# ZLG_CandleLight_F072.net
KiCad netlist of a schematic drawn in Altium Designer
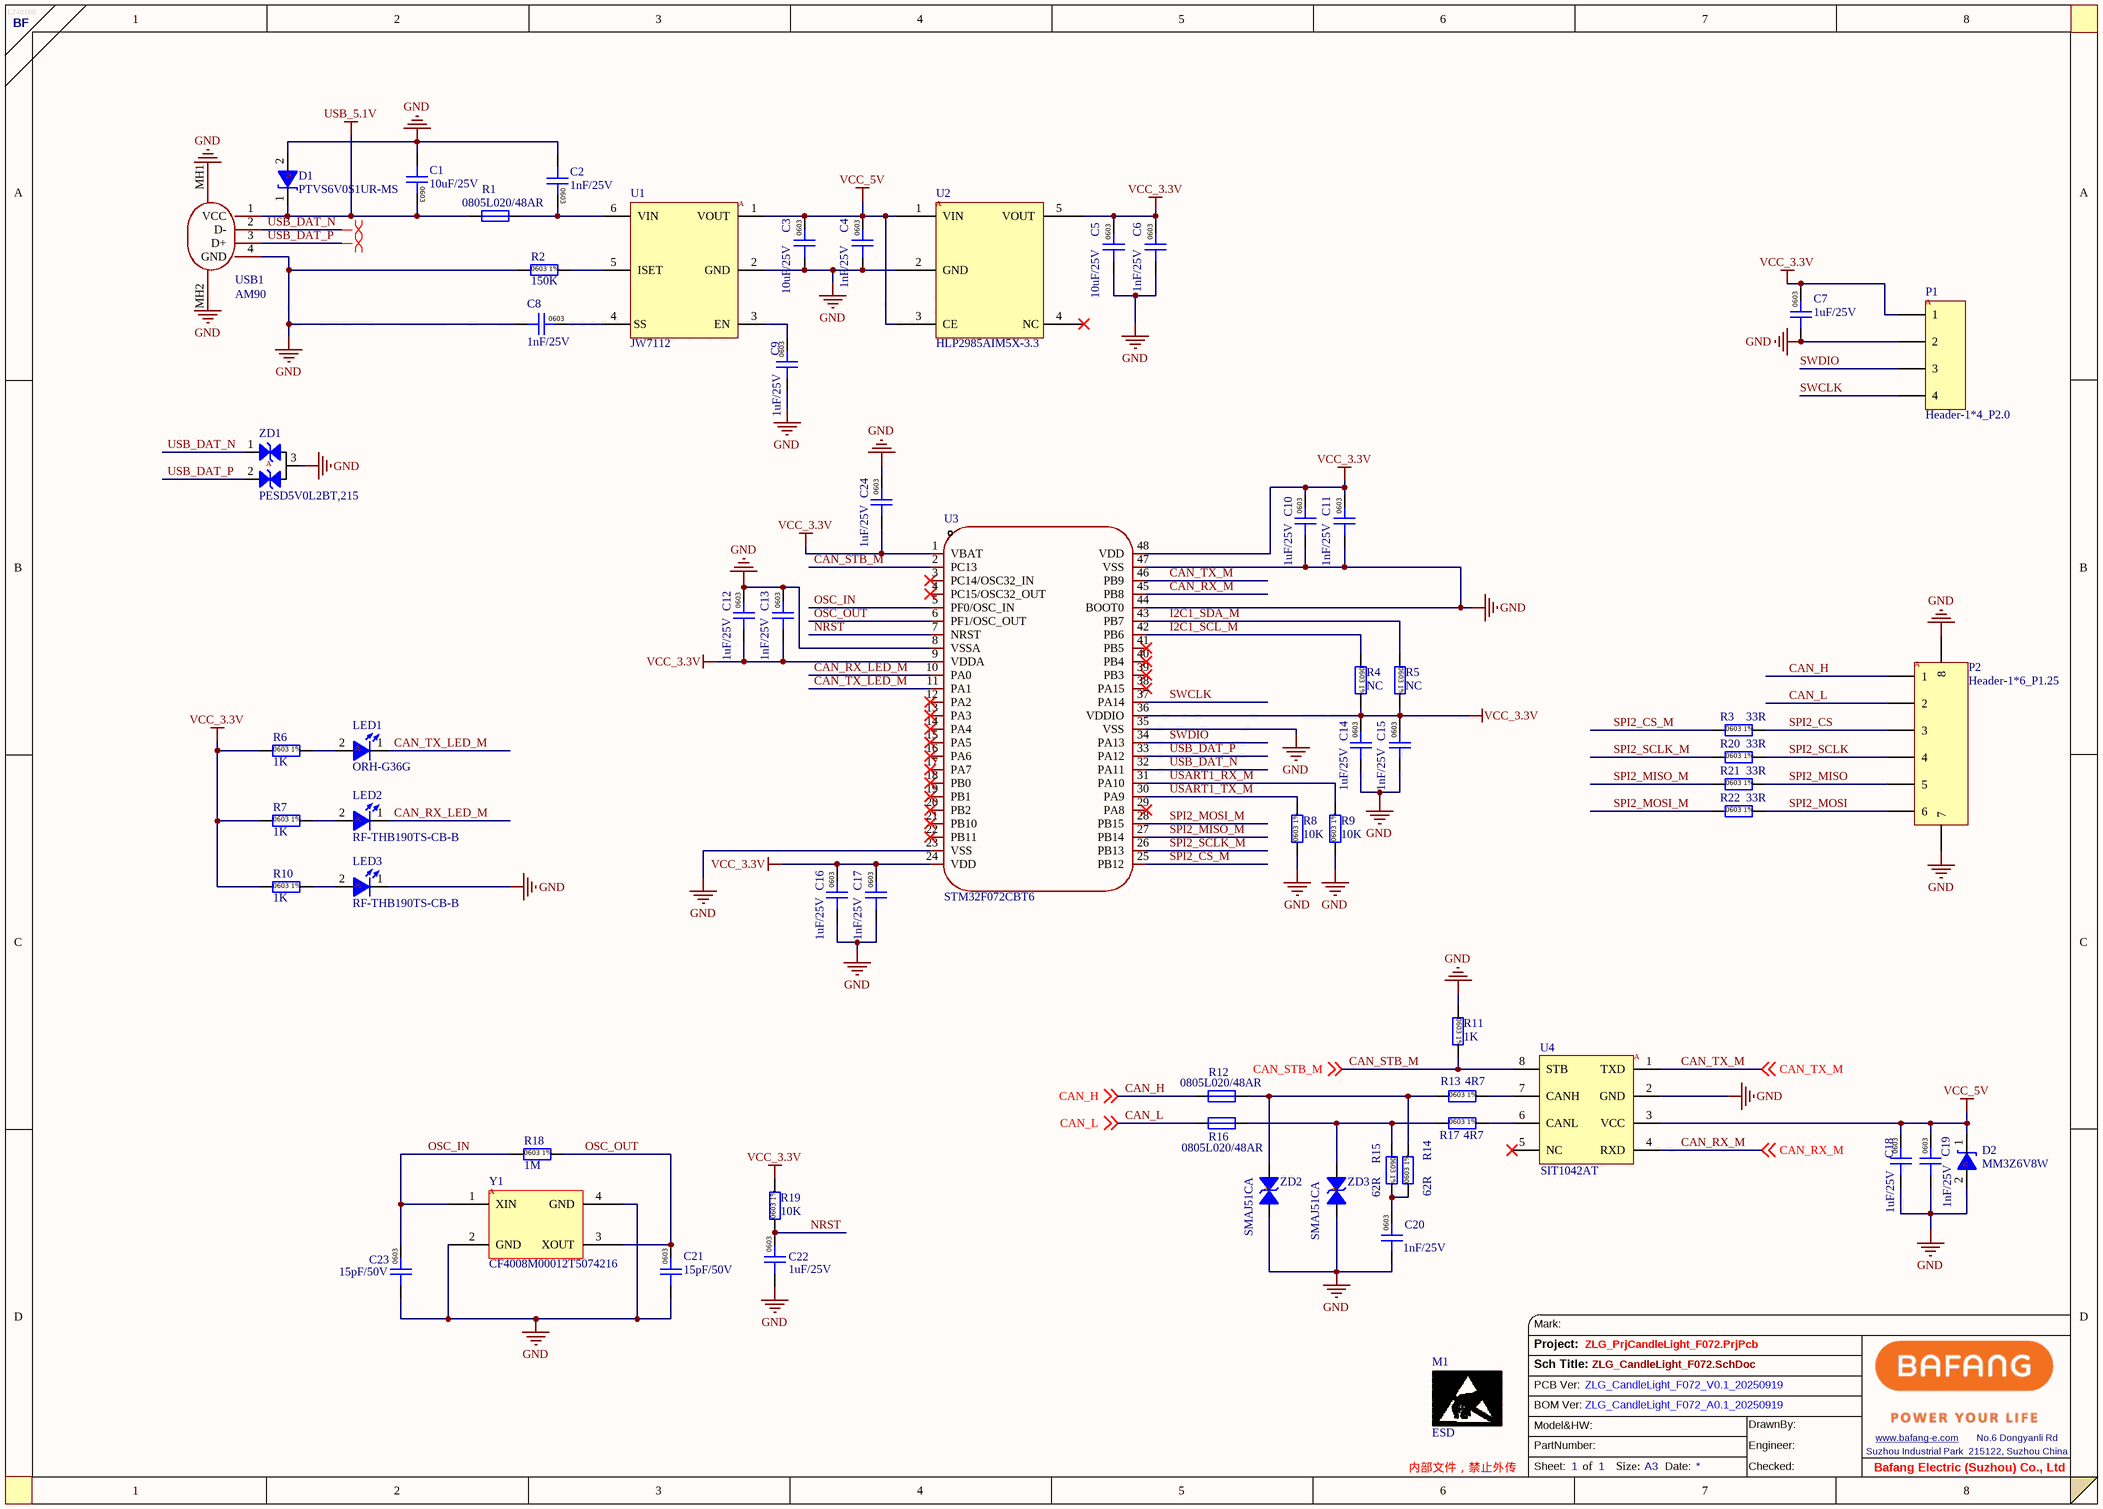
[diagram p0: ZLG_CandleLight_F072.SchDoc]

(export (version "E")
  (design (tool "Eeschema 10.0.6"))
  (components
    (comp (ref "C1")
      (value "10uF/25V")
      (footprint "C-0603")
      (description "10μF, 25V, ±10%, -55to85℃")
      (libsource (lib "Database_Lib") (part "CC0603K106-8"))
    )
    (comp (ref "C2")
      (value "1nF/25V")
      (footprint "C-0603")
      (description "1nF, 25V, ±10%, -55to125℃")
      (libsource (lib "Database_Lib") (part "CC0603K102-8"))
    )
    (comp (ref "C3")
      (value "10uF/25V")
      (footprint "C-0603")
      (description "10μF, 25V, ±10%, -55to85℃")
      (libsource (lib "Database_Lib") (part "CC0603K106-8"))
    )
    (comp (ref "C4")
      (value "1nF/25V")
      (footprint "C-0603")
      (description "1nF, 25V, ±10%, -55to125℃")
      (libsource (lib "Database_Lib") (part "CC0603K102-8"))
    )
    (comp (ref "C5")
      (value "10uF/25V")
      (footprint "C-0603")
      (description "10μF, 25V, ±10%, -55to85℃")
      (libsource (lib "Database_Lib") (part "CC0603K106-8"))
    )
    (comp (ref "C6")
      (value "1nF/25V")
      (footprint "C-0603")
      (description "1nF, 25V, ±10%, -55to125℃")
      (libsource (lib "Database_Lib") (part "CC0603K102-8"))
    )
    (comp (ref "C7")
      (value "1uF/25V")
      (footprint "C-0603")
      (description "1μF, 25V, ±10%, -55to125℃")
      (libsource (lib "Database_Lib") (part "CC0603K105-8"))
    )
    (comp (ref "C8")
      (value "1nF/25V")
      (footprint "C-0603")
      (description "1nF, 25V, ±10%, -55to125℃")
      (libsource (lib "Database_Lib") (part "CC0603K102-8"))
    )
    (comp (ref "C9")
      (value "1uF/25V")
      (footprint "C-0603")
      (description "1μF, 25V, ±10%, -55to125℃")
      (libsource (lib "Database_Lib") (part "CC0603K105-8"))
    )
    (comp (ref "C10")
      (value "1uF/25V")
      (footprint "C-0603")
      (description "1μF, 25V, ±10%, -55to125℃")
      (libsource (lib "Database_Lib") (part "CC0603K105-8"))
    )
    (comp (ref "C11")
      (value "1nF/25V")
      (footprint "C-0603")
      (description "1nF, 25V, ±10%, -55to125℃")
      (libsource (lib "Database_Lib") (part "CC0603K102-8"))
    )
    (comp (ref "C12")
      (value "1uF/25V")
      (footprint "C-0603")
      (description "1μF, 25V, ±10%, -55to125℃")
      (libsource (lib "Database_Lib") (part "CC0603K105-8"))
    )
    (comp (ref "C13")
      (value "1nF/25V")
      (footprint "C-0603")
      (description "1nF, 25V, ±10%, -55to125℃")
      (libsource (lib "Database_Lib") (part "CC0603K102-8"))
    )
    (comp (ref "C14")
      (value "1uF/25V")
      (footprint "C-0603")
      (description "1μF, 25V, ±10%, -55to125℃")
      (libsource (lib "Database_Lib") (part "CC0603K105-8"))
    )
    (comp (ref "C15")
      (value "1nF/25V")
      (footprint "C-0603")
      (description "1nF, 25V, ±10%, -55to125℃")
      (libsource (lib "Database_Lib") (part "CC0603K102-8"))
    )
    (comp (ref "C16")
      (value "1uF/25V")
      (footprint "C-0603")
      (description "1μF, 25V, ±10%, -55to125℃")
      (libsource (lib "Database_Lib") (part "CC0603K105-8"))
    )
    (comp (ref "C17")
      (value "1nF/25V")
      (footprint "C-0603")
      (description "1nF, 25V, ±10%, -55to125℃")
      (libsource (lib "Database_Lib") (part "CC0603K102-8"))
    )
    (comp (ref "C18")
      (value "1uF/25V")
      (footprint "C-0603")
      (description "1μF, 25V, ±10%, -55to125℃")
      (libsource (lib "Database_Lib") (part "CC0603K105-8"))
    )
    (comp (ref "C19")
      (value "1nF/25V")
      (footprint "C-0603")
      (description "1nF, 25V, ±10%, -55to125℃")
      (libsource (lib "Database_Lib") (part "CC0603K102-8"))
    )
    (comp (ref "C20")
      (value "1nF/25V")
      (footprint "C-0603")
      (description "1nF, 25V, ±10%, -55to125℃")
      (libsource (lib "Database_Lib") (part "CC0603K102-8"))
    )
    (comp (ref "C21")
      (value "15pF/50V")
      (footprint "C-0603")
      (description "15pF, 50V, ±5%,, -55to125℃")
      (libsource (lib "Database_Lib") (part "CC0603J150-9"))
    )
    (comp (ref "C22")
      (value "1uF/25V")
      (footprint "C-0603")
      (description "1μF, 25V, ±10%, -55to125℃")
      (libsource (lib "Database_Lib") (part "CC0603K105-8"))
    )
    (comp (ref "C23")
      (value "15pF/50V")
      (footprint "C-0603")
      (description "15pF, 50V, ±5%,, -55to125℃")
      (libsource (lib "Database_Lib") (part "CC0603J150-9"))
    )
    (comp (ref "C24")
      (value "1uF/25V")
      (footprint "C-0603")
      (description "1μF, 25V, ±10%, -55to125℃")
      (libsource (lib "Database_Lib") (part "CC0603K105-8"))
    )
    (comp (ref "D1")
      (value "PTVS6V0S1UR-MS")
      (footprint "SOD-123W")
      (description "TVS管 VR=6V,峰值脉冲电流（IPP）=38.84A,最大钳位电压:：10.3V")
      (fields
        (field (name "COMPONENTLINK1URL") "O:\\ECU\\B02_Hardware硬件\\A02_Libraries 原理图PCB封装库\\Datasheet\\Semicon\\TVS二极管_PTVS5V0S1UR-MS.PDF")
      )
      (libsource (lib "Database_Lib") (part "PTVS6V0S1UR-MS"))
    )
    (comp (ref "D2")
      (value "MM3Z6V8W")
      (footprint "SOD-123")
      (description "稳压二极管   Vzt:6.8V,  ±5%    0.5W  Izt:5mA,-65to150℃")
      (fields
        (field (name "MPN") "MM1Z6V8W")
        (field (name "COMPONENTLINK1URL") "O:\\ECU\\B02_Hardware硬件\\A02_Libraries 原理图PCB封装库\\Datasheet\\Semicon\\稳压二极管_MM1Z2V0W-MM1Z75W.pdf")
      )
      (libsource (lib "Database_Lib") (part "MM1Z6V8W"))
    )
    (comp (ref "LED1")
      (value "ORH-G36G")
      (footprint "LED-SMT-0603")
      (description "发光二极管  GREEN, 2.8V, 30mA, -25to80℃")
      (fields
        (field (name "COMPONENTLINK1URL") "O:\\ECU\\B02_Hardware硬件\\A02_Libraries 原理图PCB封装库\\Datasheet\\Semicon\\发光二极管_ORH-G36G.pdf")
      )
      (libsource (lib "Database_Lib") (part "ORH-G36G"))
    )
    (comp (ref "LED2")
      (value "RF-THB190TS-CB-B")
      (footprint "LED-SMT-0603")
      (description "发光二极管  GREEN, 2.8V, -40to85℃")
      (fields
        (field (name "COMPONENTLINK1URL") "O:\\ECU\\B02_Hardware硬件\\A02_Libraries 原理图PCB封装库\\Datasheet\\Semicon\\发光二极管_RF-THB190TS-CB-B.pdf")
      )
      (libsource (lib "Database_Lib") (part "RF-THB190TS-CB-B"))
    )
    (comp (ref "LED3")
      (value "RF-THB190TS-CB-B")
      (footprint "LED-SMT-0603")
      (description "发光二极管  GREEN, 2.8V, -40to85℃")
      (fields
        (field (name "COMPONENTLINK1URL") "O:\\ECU\\B02_Hardware硬件\\A02_Libraries 原理图PCB封装库\\Datasheet\\Semicon\\发光二极管_RF-THB190TS-CB-B.pdf")
      )
      (libsource (lib "Database_Lib") (part "RF-THB190TS-CB-B"))
    )
    (comp (ref "M1") (value "ESD") (footprint "ESD-5*4mm") (libsource (lib "Database_Lib") (part "ESD")))
    (comp (ref "P1")
      (value "Header-1*4_P2.0")
      (footprint "CON-1*4-P2.0-Download")
      (description "Header, 4Pin .P2.0")
      (libsource (lib "Database_Lib") (part "Header-1*4_P2.0"))
    )
    (comp (ref "P2")
      (value "Header-1*6_P1.25")
      (footprint "CON-1*6-P1.25")
      (description "Header, 6Pin, P1.25")
      (fields
        (field (name "MPN") "A12514WR-S-06PNLNT1T00R")
        (field (name "COMPONENTLINK1URL") "O:\\ECU\\B02_Hardware硬件\\A02_Libraries 原理图PCB封装库\\Datasheet\\Connectors\\线对板针座_A12514WR-S-06PNLNT1T00R.PDF")
      )
      (libsource (lib "Database_Lib") (part "Header-1*6_P1.25"))
    )
    (comp (ref "R1")
      (value "0805L020/48AR")
      (footprint "R-0805")
      (description "自恢复保险丝  耐压: 48V  最大电流: 40A  保持电流(Ih): 200mA  跳闸电流: 500mA")
      (fields
        (field (name "COMPONENTLINK1URL") "O:\\ECU\\B02_Hardware硬件\\A02_Libraries 原理图PCB封装库\\Datasheet\\RLC\\自恢复保险丝_0805L020-48AR.PDF")
      )
      (libsource (lib "Database_Lib") (part "F0805-020-48V"))
    )
    (comp (ref "R2")
      (value "150K")
      (footprint "R-0603")
      (description "150KΩ, 0.1W, 1%, -55to155℃")
      (libsource (lib "Database_Lib") (part "RC0603F150K"))
    )
    (comp (ref "R3")
      (value "33R")
      (footprint "R-0603")
      (description "33Ω, 0.1W, 1%, -55to155℃")
      (libsource (lib "Database_Lib") (part "RC0603F33R"))
    )
    (comp (ref "R4")
      (value "NC")
      (footprint "R-0603")
      (description "10KΩ, 0.1W, 1%, -55to155℃")
      (libsource (lib "Database_Lib") (part "RC0603F10K"))
    )
    (comp (ref "R5")
      (value "NC")
      (footprint "R-0603")
      (description "10KΩ, 0.1W, 1%, -55to155℃")
      (libsource (lib "Database_Lib") (part "RC0603F10K"))
    )
    (comp (ref "R6")
      (value "1K")
      (footprint "R-0603")
      (description "1KΩ, 0.1W, 1%, -55to155℃")
      (libsource (lib "") (part "RC0603F1K_1"))
    )
    (comp (ref "R7")
      (value "1K")
      (footprint "R-0603")
      (description "1KΩ, 0.1W, 1%, -55to155℃")
      (libsource (lib "") (part "RC0603F1K_1"))
    )
    (comp (ref "R8")
      (value "10K")
      (footprint "R-0603")
      (description "10KΩ, 0.1W, 1%, -55to155℃")
      (libsource (lib "") (part "RC0603F10K_1"))
    )
    (comp (ref "R9")
      (value "10K")
      (footprint "R-0603")
      (description "10KΩ, 0.1W, 1%, -55to155℃")
      (libsource (lib "") (part "RC0603F10K_1"))
    )
    (comp (ref "R10")
      (value "1K")
      (footprint "R-0603")
      (description "1KΩ, 0.1W, 1%, -55to155℃")
      (libsource (lib "") (part "RC0603F1K_1"))
    )
    (comp (ref "R11")
      (value "1K")
      (footprint "R-0603")
      (description "1KΩ, 0.1W, 1%, -55to155℃")
      (libsource (lib "Database_Lib") (part "RC0603F1K"))
    )
    (comp (ref "R12")
      (value "0805L020/48AR")
      (footprint "R-0805")
      (description "自恢复保险丝  耐压: 48V  最大电流: 40A  保持电流(Ih): 200mA  跳闸电流: 500mA")
      (fields
        (field (name "COMPONENTLINK1URL") "O:\\ECU\\B02_Hardware硬件\\A02_Libraries 原理图PCB封装库\\Datasheet\\RLC\\自恢复保险丝_0805L020-48AR.PDF")
      )
      (libsource (lib "Database_Lib") (part "F0805-020-48V"))
    )
    (comp (ref "R13")
      (value "4R7")
      (footprint "R-0603")
      (description "4.7Ω, 0.1W, 1%, -55to155℃")
      (libsource (lib "Database_Lib") (part "RC0603F4R7"))
    )
    (comp (ref "R14")
      (value "62R")
      (footprint "R-0603")
      (description "62Ω, 0.1W, 1%, -55to155℃")
      (libsource (lib "Database_Lib") (part "RC0603F62R"))
    )
    (comp (ref "R15")
      (value "62R")
      (footprint "R-0603")
      (description "62Ω, 0.1W, 1%, -55to155℃")
      (libsource (lib "") (part "RC0603F62R_1"))
    )
    (comp (ref "R16")
      (value "0805L020/48AR")
      (footprint "R-0805")
      (description "自恢复保险丝  耐压: 48V  最大电流: 40A  保持电流(Ih): 200mA  跳闸电流: 500mA")
      (fields
        (field (name "COMPONENTLINK1URL") "O:\\ECU\\B02_Hardware硬件\\A02_Libraries 原理图PCB封装库\\Datasheet\\RLC\\自恢复保险丝_0805L020-48AR.PDF")
      )
      (libsource (lib "Database_Lib") (part "F0805-020-48V"))
    )
    (comp (ref "R17")
      (value "4R7")
      (footprint "R-0603")
      (description "4.7Ω, 0.1W, 1%, -55to155℃")
      (libsource (lib "Database_Lib") (part "RC0603F4R7"))
    )
    (comp (ref "R18")
      (value "1M")
      (footprint "R-0603")
      (description "1MΩ, 0.1W, 1%, -55to155℃")
      (libsource (lib "Database_Lib") (part "RC0603F1M"))
    )
    (comp (ref "R19")
      (value "10K")
      (footprint "R-0603")
      (description "10KΩ, 0.1W, 1%, -55to155℃")
      (libsource (lib "") (part "RC0603F10K_1"))
    )
    (comp (ref "R20")
      (value "33R")
      (footprint "R-0603")
      (description "33Ω, 0.1W, 1%, -55to155℃")
      (libsource (lib "Database_Lib") (part "RC0603F33R"))
    )
    (comp (ref "R21")
      (value "33R")
      (footprint "R-0603")
      (description "33Ω, 0.1W, 1%, -55to155℃")
      (libsource (lib "Database_Lib") (part "RC0603F33R"))
    )
    (comp (ref "R22")
      (value "33R")
      (footprint "R-0603")
      (description "33Ω, 0.1W, 1%, -55to155℃")
      (libsource (lib "Database_Lib") (part "RC0603F33R"))
    )
    (comp (ref "U1")
      (value "JW7112")
      (footprint "SOT-23-6")
      (description "高边热插拔控制器   工作电压范围：2.8V至16V，导通电阻：50mΩ，最大3A可持续电流")
      (fields
        (field (name "COMPONENTLINK1URL") "O:\\ECU\\B02_Hardware硬件\\A02_Libraries 原理图PCB封装库\\Datasheet\\IC\\高边热插拔控制器_JW7112.pdf")
      )
      (libsource (lib "Database_Lib") (part "JW7112"))
    )
    (comp (ref "U2")
      (value "HLP2985AIM5X-3.3")
      (footprint "SOT-23-5")
      (description "LDO,工作电压16V，输出电压3.3V，输出电流150mA，-40℃~+125℃")
      (fields
        (field (name "COMPONENTLINK1URL") "O:\\ECU\\B02_Hardware硬件\\A02_Libraries 原理图PCB封装库\\Datasheet\\IC\\LDO_HLP2985AIM5X-3.3.pdf")
      )
      (libsource (lib "Database_Lib") (part "HLP2985AIM5X-3.3"))
    )
    (comp (ref "U3")
      (value "STM32F072CBT6")
      (footprint "LQFP-48_L7.0-W7.0-P0.50-LS9.0-BL")
      (fields (field (name "MANUFACTURER") "ST(意法半导体)"))
      (libsource (lib "ZLG_CandleLight_F072") (part "STM32F072CBT6"))
    )
    (comp (ref "U4")
      (value "SIT1042AT")
      (footprint "SOP-8")
      (description "CAN芯片   5V 供电，±70V 总线耐压，待机模式CAN FD 总线收发器")
      (fields
        (field (name "COMPONENTLINK1URL") "O:\\ECU\\B02_Hardware硬件\\A02_Libraries 原理图PCB封装库\\Datasheet\\IC\\CAN芯片_SIT1042AT.pdf")
      )
      (libsource (lib "Database_Lib") (part "SIT1042AT"))
    )
    (comp (ref "USB1")
      (value "AM90")
      (footprint "USB-AM-TH_AM90")
      (fields (field (name "MANUFACTURER") "SHOU HAN(首韩)"))
      (libsource (lib "ZLG_CandleLight_F072") (part "AM90"))
    )
    (comp (ref "Y1")
      (value "CF4008M00012T5074216")
      (footprint "CRYSTAL-SMT_3225-4P")
      (description "8MHZ,SMD_3225,贴片无源晶振")
      (fields
        (field (name "COMPONENTLINK1URL") "O:\\ECU\\B02_Hardware硬件\\A02_Libraries 原理图PCB封装库\\Datasheet\\Semicon\\晶振_CF4008M00012T5074216.PDF")
      )
      (libsource (lib "Database_Lib") (part "CF4008M00012T5074216"))
    )
    (comp (ref "ZD1")
      (value "PESD5V0L2BT,215")
      (footprint "SOT-23-3")
      (description "静电放电(ESD)保护管  Vbr:8.2V, Vrwm:5V, TVS二极管 1uA 5V, -65°C-150°C,")
      (fields
        (field (name "COMPONENTLINK1URL") "O:\\ECU\\B02_Hardware硬件\\A02_Libraries 原理图PCB封装库\\Datasheet\\Semicon\\TVS二极管_PESD5V0L2BT,215.pdf")
      )
      (libsource (lib "Database_Lib") (part "PESD5V0L2BT,215"))
    )
    (comp (ref "ZD2")
      (value "SMAJ51CA")
      (footprint "SMA(DO-214AC)")
      (fields
        (field (name "COMPONENTLINK1URL") "O:\\ECU\\B02_Hardware硬件\\A02_Libraries 原理图PCB封装库\\Datasheet\\Semicon\\TVS二极管_SMAJ51CA.pdf")
      )
      (libsource (lib "Database_Lib") (part "SMAJ51CA"))
    )
    (comp (ref "ZD3")
      (value "SMAJ51CA")
      (footprint "SMA(DO-214AC)")
      (fields
        (field (name "COMPONENTLINK1URL") "O:\\ECU\\B02_Hardware硬件\\A02_Libraries 原理图PCB封装库\\Datasheet\\Semicon\\TVS二极管_SMAJ51CA.pdf")
      )
      (libsource (lib "Database_Lib") (part "SMAJ51CA"))
    )
  )
  (nets
    (net (code "1") (name "/CAN_RX_LED_M") (class "Default")
      (node (ref "LED2") (pin "1") (pinfunction "C_1") (pintype "passive"))
      (node (ref "U3") (pin "10") (pinfunction "PA0_10") (pintype "passive"))
    )
    (net (code "2") (name "/CAN_TX_LED_M") (class "Default")
      (node (ref "LED1") (pin "1") (pinfunction "C_1") (pintype "passive"))
      (node (ref "U3") (pin "11") (pinfunction "PA1_11") (pintype "passive"))
    )
    (net (code "3") (name "/I2C1_SCL_M") (class "Default")
      (node (ref "R4") (pin "1") (pinfunction "1_1") (pintype "passive"))
      (node (ref "U3") (pin "42") (pinfunction "PB6_42") (pintype "passive"))
    )
    (net (code "4") (name "/I2C1_SDA_M") (class "Default")
      (node (ref "R5") (pin "1") (pinfunction "1_1") (pintype "passive"))
      (node (ref "U3") (pin "43") (pinfunction "PB7_43") (pintype "passive"))
    )
    (net (code "5") (name "/NRST") (class "Default")
      (node (ref "C22") (pin "2") (pinfunction "2_2") (pintype "passive"))
      (node (ref "R19") (pin "1") (pinfunction "1_1") (pintype "passive"))
      (node (ref "U3") (pin "7") (pinfunction "NRST_7") (pintype "passive"))
    )
    (net (code "6") (name "/OSC_IN") (class "Default")
      (node (ref "C23") (pin "2") (pinfunction "2_2") (pintype "passive"))
      (node (ref "R18") (pin "1") (pinfunction "1_1") (pintype "passive"))
      (node (ref "U3") (pin "5") (pinfunction "PF0/OSC_IN_5") (pintype "passive"))
      (node (ref "Y1") (pin "1") (pinfunction "XIN_1") (pintype "passive"))
    )
    (net (code "7") (name "/OSC_OUT") (class "Default")
      (node (ref "C21") (pin "2") (pinfunction "2_2") (pintype "passive"))
      (node (ref "R18") (pin "2") (pinfunction "2_2") (pintype "passive"))
      (node (ref "U3") (pin "6") (pinfunction "PF1/OSC_OUT_6") (pintype "passive"))
      (node (ref "Y1") (pin "3") (pinfunction "XOUT_3") (pintype "passive"))
    )
    (net (code "8") (name "/SPI2_CS") (class "Default")
      (node (ref "P2") (pin "3") (pinfunction "3_3") (pintype "passive"))
      (node (ref "R3") (pin "2") (pinfunction "2_2") (pintype "passive"))
    )
    (net (code "9") (name "/SPI2_CS_M") (class "Default")
      (node (ref "R3") (pin "1") (pinfunction "1_1") (pintype "passive"))
      (node (ref "U3") (pin "25") (pinfunction "PB12_25") (pintype "passive"))
    )
    (net (code "10") (name "/SPI2_MISO") (class "Default")
      (node (ref "P2") (pin "5") (pinfunction "5_5") (pintype "passive"))
      (node (ref "R21") (pin "2") (pinfunction "2_2") (pintype "passive"))
    )
    (net (code "11") (name "/SPI2_MISO_M") (class "Default")
      (node (ref "R21") (pin "1") (pinfunction "1_1") (pintype "passive"))
      (node (ref "U3") (pin "27") (pinfunction "PB14_27") (pintype "passive"))
    )
    (net (code "12") (name "/SPI2_MOSI") (class "Default")
      (node (ref "P2") (pin "6") (pinfunction "6_6") (pintype "passive"))
      (node (ref "R22") (pin "2") (pinfunction "2_2") (pintype "passive"))
    )
    (net (code "13") (name "/SPI2_MOSI_M") (class "Default")
      (node (ref "R22") (pin "1") (pinfunction "1_1") (pintype "passive"))
      (node (ref "U3") (pin "28") (pinfunction "PB15_28") (pintype "passive"))
    )
    (net (code "14") (name "/SPI2_SCLK") (class "Default")
      (node (ref "P2") (pin "4") (pinfunction "4_4") (pintype "passive"))
      (node (ref "R20") (pin "2") (pinfunction "2_2") (pintype "passive"))
    )
    (net (code "15") (name "/SPI2_SCLK_M") (class "Default")
      (node (ref "R20") (pin "1") (pinfunction "1_1") (pintype "passive"))
      (node (ref "U3") (pin "26") (pinfunction "PB13_26") (pintype "passive"))
    )
    (net (code "16") (name "/SWCLK") (class "Default")
      (node (ref "P1") (pin "4") (pinfunction "4_4") (pintype "passive"))
      (node (ref "U3") (pin "37") (pinfunction "PA14_37") (pintype "passive"))
    )
    (net (code "17") (name "/SWDIO") (class "Default")
      (node (ref "P1") (pin "3") (pinfunction "3_3") (pintype "passive"))
      (node (ref "U3") (pin "34") (pinfunction "PA13_34") (pintype "passive"))
    )
    (net (code "18") (name "/USART1_RX_M") (class "Default")
      (node (ref "R9") (pin "2") (pinfunction "2_2") (pintype "passive"))
      (node (ref "U3") (pin "31") (pinfunction "PA10_31") (pintype "passive"))
    )
    (net (code "19") (name "/USART1_TX_M") (class "Default")
      (node (ref "R8") (pin "2") (pinfunction "2_2") (pintype "passive"))
      (node (ref "U3") (pin "30") (pinfunction "PA9_30") (pintype "passive"))
    )
    (net (code "20") (name "/USB_DAT_N") (class "Default")
      (node (ref "U3") (pin "32") (pinfunction "PA11_32") (pintype "passive"))
      (node (ref "USB1") (pin "2") (pinfunction "D-_2") (pintype "passive"))
      (node (ref "ZD1") (pin "1") (pinfunction "1_1") (pintype "passive"))
    )
    (net (code "21") (name "/USB_DAT_P") (class "Default")
      (node (ref "U3") (pin "33") (pinfunction "PA12_33") (pintype "passive"))
      (node (ref "USB1") (pin "3") (pinfunction "D+_3") (pintype "passive"))
      (node (ref "ZD1") (pin "2") (pinfunction "2_2") (pintype "passive"))
    )
    (net (code "22") (name "CAN_H") (class "Default")
      (node (ref "P2") (pin "1") (pinfunction "1_1") (pintype "passive"))
      (node (ref "R12") (pin "1") (pinfunction "1_1") (pintype "passive"))
    )
    (net (code "23") (name "CAN_L") (class "Default")
      (node (ref "P2") (pin "2") (pinfunction "2_2") (pintype "passive"))
      (node (ref "R16") (pin "1") (pinfunction "1_1") (pintype "passive"))
    )
    (net (code "24") (name "CAN_RX_M") (class "Default")
      (node (ref "U3") (pin "45") (pinfunction "PB8_45") (pintype "passive"))
      (node (ref "U4") (pin "4") (pinfunction "RXD_4") (pintype "passive"))
    )
    (net (code "25") (name "CAN_STB_M") (class "Default")
      (node (ref "R11") (pin "2") (pinfunction "2_2") (pintype "passive"))
      (node (ref "U3") (pin "2") (pinfunction "PC13_2") (pintype "passive"))
      (node (ref "U4") (pin "8") (pinfunction "STB_8") (pintype "passive"))
    )
    (net (code "26") (name "CAN_TX_M") (class "Default")
      (node (ref "U3") (pin "46") (pinfunction "PB9_46") (pintype "passive"))
      (node (ref "U4") (pin "1") (pinfunction "TXD_1") (pintype "passive"))
    )
    (net (code "27") (name "GND") (class "Default")
      (node (ref "C1") (pin "1") (pinfunction "1_1") (pintype "passive"))
      (node (ref "C10") (pin "1") (pinfunction "1_1") (pintype "passive"))
      (node (ref "C11") (pin "1") (pinfunction "1_1") (pintype "passive"))
      (node (ref "C12") (pin "2") (pinfunction "2_2") (pintype "passive"))
      (node (ref "C13") (pin "2") (pinfunction "2_2") (pintype "passive"))
      (node (ref "C14") (pin "1") (pinfunction "1_1") (pintype "passive"))
      (node (ref "C15") (pin "1") (pinfunction "1_1") (pintype "passive"))
      (node (ref "C16") (pin "1") (pinfunction "1_1") (pintype "passive"))
      (node (ref "C17") (pin "1") (pinfunction "1_1") (pintype "passive"))
      (node (ref "C18") (pin "1") (pinfunction "1_1") (pintype "passive"))
      (node (ref "C19") (pin "1") (pinfunction "1_1") (pintype "passive"))
      (node (ref "C2") (pin "1") (pinfunction "1_1") (pintype "passive"))
      (node (ref "C20") (pin "1") (pinfunction "1_1") (pintype "passive"))
      (node (ref "C21") (pin "1") (pinfunction "1_1") (pintype "passive"))
      (node (ref "C22") (pin "1") (pinfunction "1_1") (pintype "passive"))
      (node (ref "C23") (pin "1") (pinfunction "1_1") (pintype "passive"))
      (node (ref "C24") (pin "2") (pinfunction "2_2") (pintype "passive"))
      (node (ref "C3") (pin "1") (pinfunction "1_1") (pintype "passive"))
      (node (ref "C4") (pin "1") (pinfunction "1_1") (pintype "passive"))
      (node (ref "C5") (pin "1") (pinfunction "1_1") (pintype "passive"))
      (node (ref "C6") (pin "1") (pinfunction "1_1") (pintype "passive"))
      (node (ref "C7") (pin "1") (pinfunction "1_1") (pintype "passive"))
      (node (ref "C8") (pin "1") (pinfunction "1_1") (pintype "passive"))
      (node (ref "C9") (pin "1") (pinfunction "1_1") (pintype "passive"))
      (node (ref "D1") (pin "2") (pinfunction "A_2") (pintype "passive"))
      (node (ref "D2") (pin "2") (pinfunction "A_2") (pintype "passive"))
      (node (ref "LED3") (pin "1") (pinfunction "C_1") (pintype "passive"))
      (node (ref "P1") (pin "2") (pinfunction "2_2") (pintype "passive"))
      (node (ref "P2") (pin "7") (pinfunction "7_7") (pintype "passive"))
      (node (ref "P2") (pin "8") (pinfunction "8_8") (pintype "passive"))
      (node (ref "R11") (pin "1") (pinfunction "1_1") (pintype "passive"))
      (node (ref "R2") (pin "1") (pinfunction "1_1") (pintype "passive"))
      (node (ref "R8") (pin "1") (pinfunction "1_1") (pintype "passive"))
      (node (ref "R9") (pin "1") (pinfunction "1_1") (pintype "passive"))
      (node (ref "U1") (pin "2") (pinfunction "GND_2") (pintype "passive"))
      (node (ref "U2") (pin "2") (pinfunction "GND_2") (pintype "passive"))
      (node (ref "U3") (pin "23") (pinfunction "VSS_23") (pintype "passive"))
      (node (ref "U3") (pin "35") (pinfunction "VSS_35") (pintype "passive"))
      (node (ref "U3") (pin "44") (pinfunction "BOOT0_44") (pintype "passive"))
      (node (ref "U3") (pin "47") (pinfunction "VSS_47") (pintype "passive"))
      (node (ref "U3") (pin "8") (pinfunction "VSSA_8") (pintype "passive"))
      (node (ref "U4") (pin "2") (pinfunction "GND_2") (pintype "passive"))
      (node (ref "USB1") (pin "4") (pinfunction "GND_4") (pintype "passive"))
      (node (ref "USB1") (pin "MH1") (pinfunction "MH1_MH1") (pintype "passive"))
      (node (ref "USB1") (pin "MH2") (pinfunction "MH2_MH2") (pintype "passive"))
      (node (ref "Y1") (pin "2") (pinfunction "GND_2") (pintype "passive"))
      (node (ref "Y1") (pin "4") (pinfunction "GND_4") (pintype "passive"))
      (node (ref "ZD1") (pin "3") (pinfunction "3_3") (pintype "passive"))
      (node (ref "ZD2") (pin "1") (pinfunction "1_1") (pintype "passive"))
      (node (ref "ZD3") (pin "1") (pinfunction "1_1") (pintype "passive"))
    )
    (net (code "28") (name "Net-(C20-Pad2)") (class "Default")
      (node (ref "C20") (pin "2") (pinfunction "2_2") (pintype "passive"))
      (node (ref "R14") (pin "1") (pinfunction "1_1") (pintype "passive"))
      (node (ref "R15") (pin "2") (pinfunction "2_2") (pintype "passive"))
    )
    (net (code "29") (name "Net-(LED1-A)") (class "Default")
      (node (ref "LED1") (pin "2") (pinfunction "A_2") (pintype "passive"))
      (node (ref "R6") (pin "2") (pinfunction "2_2") (pintype "passive"))
    )
    (net (code "30") (name "Net-(LED2-A)") (class "Default")
      (node (ref "LED2") (pin "2") (pinfunction "A_2") (pintype "passive"))
      (node (ref "R7") (pin "2") (pinfunction "2_2") (pintype "passive"))
    )
    (net (code "31") (name "Net-(LED3-A)") (class "Default")
      (node (ref "LED3") (pin "2") (pinfunction "A_2") (pintype "passive"))
      (node (ref "R10") (pin "2") (pinfunction "2_2") (pintype "passive"))
    )
    (net (code "32") (name "Net-(R12-Pad2)") (class "Default")
      (node (ref "R12") (pin "2") (pinfunction "2_2") (pintype "passive"))
      (node (ref "R13") (pin "1") (pinfunction "1_1") (pintype "passive"))
      (node (ref "R14") (pin "2") (pinfunction "2_2") (pintype "passive"))
      (node (ref "ZD2") (pin "2") (pinfunction "2_2") (pintype "passive"))
    )
    (net (code "33") (name "Net-(R15-Pad1)") (class "Default")
      (node (ref "R15") (pin "1") (pinfunction "1_1") (pintype "passive"))
      (node (ref "R16") (pin "2") (pinfunction "2_2") (pintype "passive"))
      (node (ref "R17") (pin "1") (pinfunction "1_1") (pintype "passive"))
      (node (ref "ZD3") (pin "2") (pinfunction "2_2") (pintype "passive"))
    )
    (net (code "34") (name "Net-(U1-EN)") (class "Default")
      (node (ref "C9") (pin "2") (pinfunction "2_2") (pintype "passive"))
      (node (ref "U1") (pin "3") (pinfunction "EN_3") (pintype "passive"))
    )
    (net (code "35") (name "Net-(U1-ISET)") (class "Default")
      (node (ref "R2") (pin "2") (pinfunction "2_2") (pintype "passive"))
      (node (ref "U1") (pin "5") (pinfunction "ISET_5") (pintype "passive"))
    )
    (net (code "36") (name "Net-(U1-SS)") (class "Default")
      (node (ref "C8") (pin "2") (pinfunction "2_2") (pintype "passive"))
      (node (ref "U1") (pin "4") (pinfunction "SS_4") (pintype "passive"))
    )
    (net (code "37") (name "Net-(U1-VIN)") (class "Default")
      (node (ref "C2") (pin "2") (pinfunction "2_2") (pintype "passive"))
      (node (ref "R1") (pin "2") (pinfunction "2_2") (pintype "passive"))
      (node (ref "U1") (pin "6") (pinfunction "VIN_6") (pintype "passive"))
    )
    (net (code "38") (name "Net-(U4-CANH)") (class "Default")
      (node (ref "R13") (pin "2") (pinfunction "2_2") (pintype "passive"))
      (node (ref "U4") (pin "7") (pinfunction "CANH_7") (pintype "passive"))
    )
    (net (code "39") (name "Net-(U4-CANL)") (class "Default")
      (node (ref "R17") (pin "2") (pinfunction "2_2") (pintype "passive"))
      (node (ref "U4") (pin "6") (pinfunction "CANL_6") (pintype "passive"))
    )
    (net (code "40") (name "USB_5.1V") (class "Default")
      (node (ref "C1") (pin "2") (pinfunction "2_2") (pintype "passive"))
      (node (ref "D1") (pin "1") (pinfunction "C_1") (pintype "passive"))
      (node (ref "R1") (pin "1") (pinfunction "1_1") (pintype "passive"))
      (node (ref "USB1") (pin "1") (pinfunction "VCC_1") (pintype "passive"))
    )
    (net (code "41") (name "VCC_3.3V") (class "Default")
      (node (ref "C10") (pin "2") (pinfunction "2_2") (pintype "passive"))
      (node (ref "C11") (pin "2") (pinfunction "2_2") (pintype "passive"))
      (node (ref "C12") (pin "1") (pinfunction "1_1") (pintype "passive"))
      (node (ref "C13") (pin "1") (pinfunction "1_1") (pintype "passive"))
      (node (ref "C14") (pin "2") (pinfunction "2_2") (pintype "passive"))
      (node (ref "C15") (pin "2") (pinfunction "2_2") (pintype "passive"))
      (node (ref "C16") (pin "2") (pinfunction "2_2") (pintype "passive"))
      (node (ref "C17") (pin "2") (pinfunction "2_2") (pintype "passive"))
      (node (ref "C24") (pin "1") (pinfunction "1_1") (pintype "passive"))
      (node (ref "C5") (pin "2") (pinfunction "2_2") (pintype "passive"))
      (node (ref "C6") (pin "2") (pinfunction "2_2") (pintype "passive"))
      (node (ref "C7") (pin "2") (pinfunction "2_2") (pintype "passive"))
      (node (ref "P1") (pin "1") (pinfunction "1_1") (pintype "passive"))
      (node (ref "R10") (pin "1") (pinfunction "1_1") (pintype "passive"))
      (node (ref "R19") (pin "2") (pinfunction "2_2") (pintype "passive"))
      (node (ref "R4") (pin "2") (pinfunction "2_2") (pintype "passive"))
      (node (ref "R5") (pin "2") (pinfunction "2_2") (pintype "passive"))
      (node (ref "R6") (pin "1") (pinfunction "1_1") (pintype "passive"))
      (node (ref "R7") (pin "1") (pinfunction "1_1") (pintype "passive"))
      (node (ref "U2") (pin "5") (pinfunction "VOUT_5") (pintype "passive"))
      (node (ref "U3") (pin "1") (pinfunction "VBAT_1") (pintype "passive"))
      (node (ref "U3") (pin "24") (pinfunction "VDD_24") (pintype "passive"))
      (node (ref "U3") (pin "36") (pinfunction "VDDIO_36") (pintype "passive"))
      (node (ref "U3") (pin "48") (pinfunction "VDD_48") (pintype "passive"))
      (node (ref "U3") (pin "9") (pinfunction "VDDA_9") (pintype "passive"))
    )
    (net (code "42") (name "VCC_5V") (class "Default")
      (node (ref "C18") (pin "2") (pinfunction "2_2") (pintype "passive"))
      (node (ref "C19") (pin "2") (pinfunction "2_2") (pintype "passive"))
      (node (ref "C3") (pin "2") (pinfunction "2_2") (pintype "passive"))
      (node (ref "C4") (pin "2") (pinfunction "2_2") (pintype "passive"))
      (node (ref "D2") (pin "1") (pinfunction "C_1") (pintype "passive"))
      (node (ref "U1") (pin "1") (pinfunction "VOUT_1") (pintype "passive"))
      (node (ref "U2") (pin "1") (pinfunction "VIN_1") (pintype "passive"))
      (node (ref "U2") (pin "3") (pinfunction "CE_3") (pintype "passive"))
      (node (ref "U4") (pin "3") (pinfunction "VCC_3") (pintype "passive"))
    )
    (net (code "43") (name "unconnected-(U2-NC-Pad4)") (class "Default")
      (node (ref "U2") (pin "4") (pinfunction "NC_4") (pintype "passive+no_connect"))
    )
    (net (code "44") (name "unconnected-(U3-PA2-Pad12)") (class "Default")
      (node (ref "U3") (pin "12") (pinfunction "PA2_12") (pintype "passive+no_connect"))
    )
    (net (code "45") (name "unconnected-(U3-PA3-Pad13)") (class "Default")
      (node (ref "U3") (pin "13") (pinfunction "PA3_13") (pintype "passive+no_connect"))
    )
    (net (code "46") (name "unconnected-(U3-PA4-Pad14)") (class "Default")
      (node (ref "U3") (pin "14") (pinfunction "PA4_14") (pintype "passive+no_connect"))
    )
    (net (code "47") (name "unconnected-(U3-PA5-Pad15)") (class "Default")
      (node (ref "U3") (pin "15") (pinfunction "PA5_15") (pintype "passive+no_connect"))
    )
    (net (code "48") (name "unconnected-(U3-PA6-Pad16)") (class "Default")
      (node (ref "U3") (pin "16") (pinfunction "PA6_16") (pintype "passive+no_connect"))
    )
    (net (code "49") (name "unconnected-(U3-PA7-Pad17)") (class "Default")
      (node (ref "U3") (pin "17") (pinfunction "PA7_17") (pintype "passive+no_connect"))
    )
    (net (code "50") (name "unconnected-(U3-PA8-Pad29)") (class "Default")
      (node (ref "U3") (pin "29") (pinfunction "PA8_29") (pintype "passive+no_connect"))
    )
    (net (code "51") (name "unconnected-(U3-PA15-Pad38)") (class "Default")
      (node (ref "U3") (pin "38") (pinfunction "PA15_38") (pintype "passive+no_connect"))
    )
    (net (code "52") (name "unconnected-(U3-PB0-Pad18)") (class "Default")
      (node (ref "U3") (pin "18") (pinfunction "PB0_18") (pintype "passive+no_connect"))
    )
    (net (code "53") (name "unconnected-(U3-PB1-Pad19)") (class "Default")
      (node (ref "U3") (pin "19") (pinfunction "PB1_19") (pintype "passive+no_connect"))
    )
    (net (code "54") (name "unconnected-(U3-PB2-Pad20)") (class "Default")
      (node (ref "U3") (pin "20") (pinfunction "PB2_20") (pintype "passive+no_connect"))
    )
    (net (code "55") (name "unconnected-(U3-PB3-Pad39)") (class "Default")
      (node (ref "U3") (pin "39") (pinfunction "PB3_39") (pintype "passive+no_connect"))
    )
    (net (code "56") (name "unconnected-(U3-PB4-Pad40)") (class "Default")
      (node (ref "U3") (pin "40") (pinfunction "PB4_40") (pintype "passive+no_connect"))
    )
    (net (code "57") (name "unconnected-(U3-PB5-Pad41)") (class "Default")
      (node (ref "U3") (pin "41") (pinfunction "PB5_41") (pintype "passive+no_connect"))
    )
    (net (code "58") (name "unconnected-(U3-PB10-Pad21)") (class "Default")
      (node (ref "U3") (pin "21") (pinfunction "PB10_21") (pintype "passive+no_connect"))
    )
    (net (code "59") (name "unconnected-(U3-PB11-Pad22)") (class "Default")
      (node (ref "U3") (pin "22") (pinfunction "PB11_22") (pintype "passive+no_connect"))
    )
    (net (code "60") (name "unconnected-(U3-PC14{slash}OSC32_IN-Pad3)") (class "Default")
      (node (ref "U3") (pin "3") (pinfunction "PC14/OSC32_IN_3") (pintype "passive+no_connect"))
    )
    (net (code "61") (name "unconnected-(U3-PC15{slash}OSC32_OUT-Pad4)") (class "Default")
      (node (ref "U3") (pin "4") (pinfunction "PC15/OSC32_OUT_4") (pintype "passive+no_connect"))
    )
    (net (code "62") (name "unconnected-(U4-NC-Pad5)") (class "Default")
      (node (ref "U4") (pin "5") (pinfunction "NC_5") (pintype "passive+no_connect"))
    )
  )
)
